# schem.net
KiCad netlist of a schematic drawn in Altium Designer
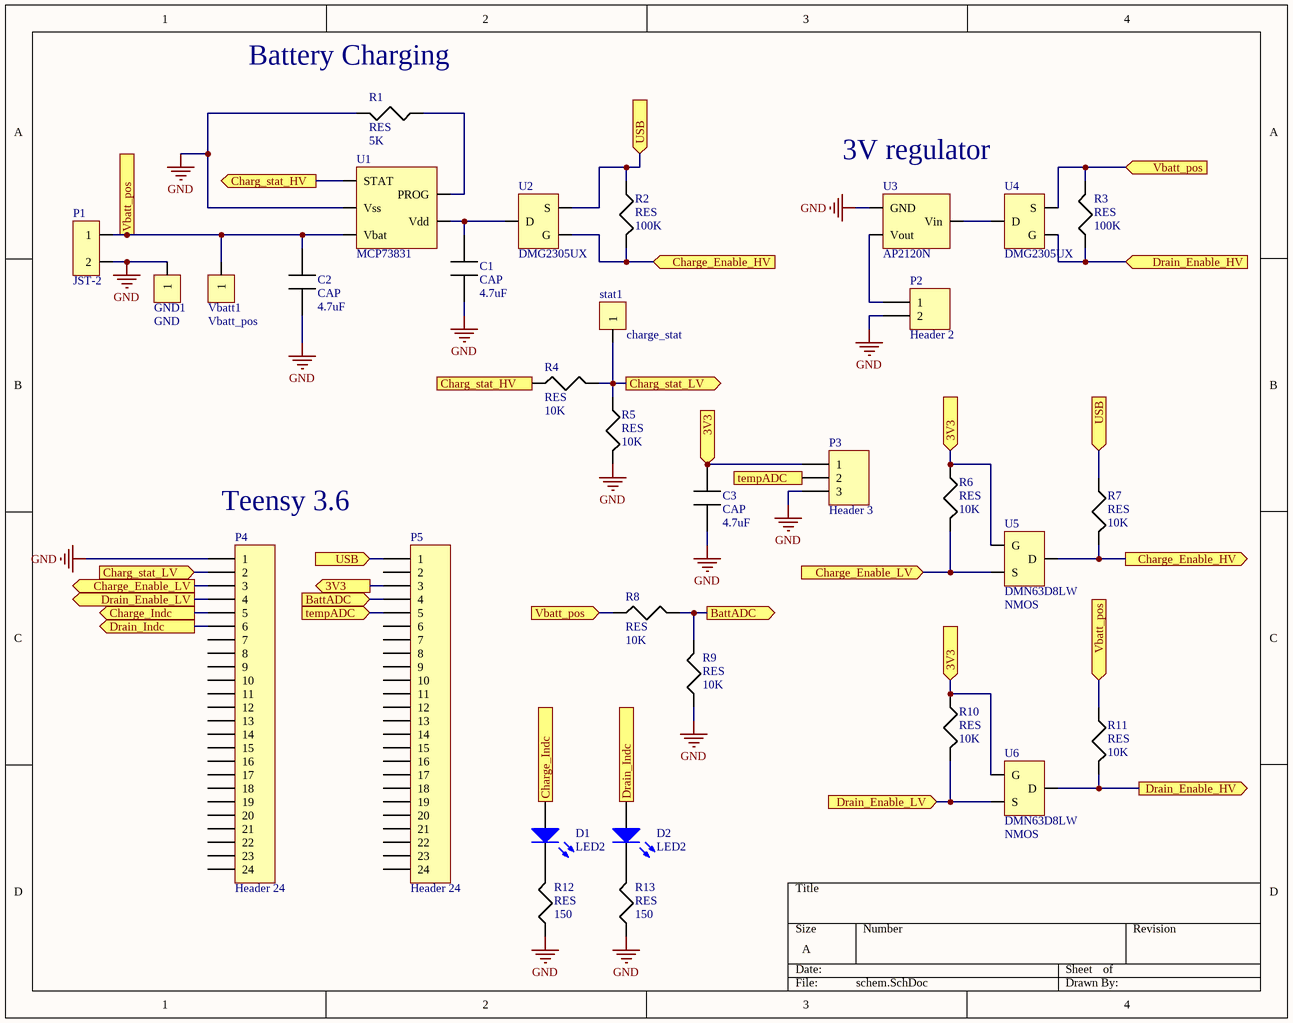
[diagram p0: schem.SchDoc]

(export (version "E")
  (design (tool "Eeschema 10.0.6"))
  (components
    (comp (ref "C1")
      (value "CAP")
      (footprint "Cap 0603 (1608 metric)")
      (fields (field (name "ALTIUM_VALUE") "4.7uF"))
      (libsource (lib "passives") (part "CAP"))
    )
    (comp (ref "C2")
      (value "CAP")
      (footprint "Cap 0603 (1608 metric)")
      (fields (field (name "ALTIUM_VALUE") "4.7uF"))
      (libsource (lib "passives") (part "CAP"))
    )
    (comp (ref "C3")
      (value "CAP")
      (footprint "Cap 0603 (1608 metric)")
      (fields (field (name "ALTIUM_VALUE") "4.7uF"))
      (libsource (lib "passives") (part "CAP"))
    )
    (comp (ref "D1")
      (value "LED2")
      (footprint "3.2X1.6X1.1")
      (description "Typical RED, GREEN, YELLOW, AMBER GaAs LED")
      (fields (field (name "PUBLISHER") "Altium Limited"))
      (libsource (lib "Miscellaneous Devices") (part "LED2"))
    )
    (comp (ref "D2")
      (value "LED2")
      (footprint "3.2X1.6X1.1")
      (description "Typical RED, GREEN, YELLOW, AMBER GaAs LED")
      (fields (field (name "PUBLISHER") "Altium Limited"))
      (libsource (lib "Miscellaneous Devices") (part "LED2"))
    )
    (comp (ref "GND1")
      (value "GND")
      (footprint "test pad")
      (description "test pad")
      (libsource (lib "test_pad") (part "test_pad"))
    )
    (comp (ref "P1") (value "JST-2") (footprint "JST-2 SMT") (libsource (lib "JST") (part "JST-2")))
    (comp (ref "P2")
      (value "Header 2")
      (footprint "HDR1X2")
      (description "Header, 2-Pin")
      (fields (field (name "PUBLISHER") "Altium Limited"))
      (libsource (lib "Miscellaneous Connectors") (part "Header 2"))
    )
    (comp (ref "P3")
      (value "Header 3")
      (footprint "HDR1X3")
      (description "Header, 3-Pin")
      (fields (field (name "PUBLISHER") "Altium Limited"))
      (libsource (lib "Miscellaneous Connectors") (part "Header 3"))
    )
    (comp (ref "P4")
      (value "Header 24")
      (footprint "HDR1X24")
      (description "Header, 24-Pin")
      (fields (field (name "PUBLISHER") "Altium Limited"))
      (libsource (lib "Miscellaneous Connectors") (part "Header 24"))
    )
    (comp (ref "P5")
      (value "Header 24")
      (footprint "HDR1X24")
      (description "Header, 24-Pin")
      (fields (field (name "PUBLISHER") "Altium Limited"))
      (libsource (lib "Miscellaneous Connectors") (part "Header 24"))
    )
    (comp (ref "R1")
      (value "RES")
      (footprint "Res 0603 (1608 metric)")
      (fields (field (name "ALTIUM_VALUE") "5K"))
      (libsource (lib "passives") (part "RES"))
    )
    (comp (ref "R2")
      (value "RES")
      (footprint "Res 0603 (1608 metric)")
      (fields (field (name "ALTIUM_VALUE") "100K"))
      (libsource (lib "passives") (part "RES"))
    )
    (comp (ref "R3")
      (value "RES")
      (footprint "Res 0603 (1608 metric)")
      (fields (field (name "ALTIUM_VALUE") "100K"))
      (libsource (lib "passives") (part "RES"))
    )
    (comp (ref "R4")
      (value "RES")
      (footprint "Res 0603 (1608 metric)")
      (fields (field (name "ALTIUM_VALUE") "10K"))
      (libsource (lib "passives") (part "RES"))
    )
    (comp (ref "R5")
      (value "RES")
      (footprint "Res 0603 (1608 metric)")
      (fields (field (name "ALTIUM_VALUE") "10K"))
      (libsource (lib "passives") (part "RES"))
    )
    (comp (ref "R6")
      (value "RES")
      (footprint "Res 0603 (1608 metric)")
      (fields (field (name "ALTIUM_VALUE") "10K"))
      (libsource (lib "passives") (part "RES"))
    )
    (comp (ref "R7")
      (value "RES")
      (footprint "Res 0603 (1608 metric)")
      (fields (field (name "ALTIUM_VALUE") "10K"))
      (libsource (lib "passives") (part "RES"))
    )
    (comp (ref "R8")
      (value "RES")
      (footprint "Res 0603 (1608 metric)")
      (fields (field (name "ALTIUM_VALUE") "10K"))
      (libsource (lib "passives") (part "RES"))
    )
    (comp (ref "R9")
      (value "RES")
      (footprint "Res 0603 (1608 metric)")
      (fields (field (name "ALTIUM_VALUE") "10K"))
      (libsource (lib "passives") (part "RES"))
    )
    (comp (ref "R10")
      (value "RES")
      (footprint "Res 0603 (1608 metric)")
      (fields (field (name "ALTIUM_VALUE") "10K"))
      (libsource (lib "passives") (part "RES"))
    )
    (comp (ref "R11")
      (value "RES")
      (footprint "Res 0603 (1608 metric)")
      (fields (field (name "ALTIUM_VALUE") "10K"))
      (libsource (lib "passives") (part "RES"))
    )
    (comp (ref "R12")
      (value "RES")
      (footprint "Res 0603 (1608 metric)")
      (fields (field (name "ALTIUM_VALUE") "150"))
      (libsource (lib "passives") (part "RES"))
    )
    (comp (ref "R13")
      (value "RES")
      (footprint "Res 0603 (1608 metric)")
      (fields (field (name "ALTIUM_VALUE") "150"))
      (libsource (lib "passives") (part "RES"))
    )
    (comp (ref "stat1")
      (value "charge_stat")
      (footprint "test pad")
      (description "test pad")
      (libsource (lib "") (part "test_pad_1"))
    )
    (comp (ref "U1")
      (value "MCP73831")
      (footprint "SOT23127P600-8N")
      (description "Li-Charge Management Controllers")
      (libsource (lib "MCP73831") (part "MCP73831"))
    )
    (comp (ref "U2")
      (value "DMG2305UX")
      (footprint "SOT105P240X110-3N")
      (description "P-MOSFET")
      (libsource (lib "Diodes-Inc-FET") (part "DMG2305UX"))
    )
    (comp (ref "U3")
      (value "AP2120N")
      (footprint "AP2120")
      (description "3.0V regulator")
      (libsource (lib "Diodes-Inc-Regulator") (part "AP2120N"))
    )
    (comp (ref "U4")
      (value "DMG2305UX")
      (footprint "SOT105P240X110-3N")
      (description "P-MOSFET")
      (libsource (lib "Diodes-Inc-FET") (part "DMG2305UX"))
    )
    (comp (ref "U5")
      (value "DMN63D8LW")
      (footprint "DMN63D8LW")
      (description "N-MOSFET SOT-323")
      (fields (field (name "ALTIUM_UNNAMED_1") "NMOS"))
      (libsource (lib "Diodes-Inc-FET") (part "DMN63D8LW"))
    )
    (comp (ref "U6")
      (value "DMN63D8LW")
      (footprint "DMN63D8LW")
      (description "N-MOSFET SOT-323")
      (fields (field (name "ALTIUM_UNNAMED_1") "NMOS"))
      (libsource (lib "Diodes-Inc-FET") (part "DMN63D8LW"))
    )
    (comp (ref "Vbatt1")
      (value "Vbatt_pos")
      (footprint "test pad")
      (description "test pad")
      (libsource (lib "test_pad") (part "test_pad"))
    )
  )
  (nets
    (net (code "1") (name "/3V3") (class "Default")
      (node (ref "C3") (pin "2") (pinfunction "2_2") (pintype "passive"))
      (node (ref "P3") (pin "1") (pinfunction "1_1") (pintype "passive"))
      (node (ref "P5") (pin "3") (pinfunction "3_3") (pintype "passive"))
      (node (ref "R10") (pin "1") (pinfunction "1_1") (pintype "passive"))
      (node (ref "R6") (pin "1") (pinfunction "1_1") (pintype "passive"))
      (node (ref "U5") (pin "1") (pinfunction "G_1") (pintype "passive"))
      (node (ref "U6") (pin "1") (pinfunction "G_1") (pintype "passive"))
    )
    (net (code "2") (name "/BattADC") (class "Default")
      (node (ref "P5") (pin "4") (pinfunction "4_4") (pintype "passive"))
      (node (ref "R8") (pin "2") (pinfunction "2_2") (pintype "passive"))
      (node (ref "R9") (pin "2") (pinfunction "2_2") (pintype "passive"))
    )
    (net (code "3") (name "/Charg_stat_HV") (class "Default")
      (node (ref "R4") (pin "1") (pinfunction "1_1") (pintype "passive"))
      (node (ref "U1") (pin "1") (pinfunction "STAT_1") (pintype "passive"))
    )
    (net (code "4") (name "/Charg_stat_LV") (class "Default")
      (node (ref "P4") (pin "2") (pinfunction "2_2") (pintype "passive"))
      (node (ref "R4") (pin "2") (pinfunction "2_2") (pintype "passive"))
      (node (ref "R5") (pin "1") (pinfunction "1_1") (pintype "passive"))
      (node (ref "stat1") (pin "1") (pinfunction "1_1") (pintype "passive"))
    )
    (net (code "5") (name "/Charge_Enable_HV") (class "Default")
      (node (ref "R2") (pin "2") (pinfunction "2_2") (pintype "passive"))
      (node (ref "R7") (pin "2") (pinfunction "2_2") (pintype "passive"))
      (node (ref "U2") (pin "1") (pinfunction "G_1") (pintype "passive"))
      (node (ref "U5") (pin "3") (pinfunction "D_3") (pintype "passive"))
    )
    (net (code "6") (name "/Charge_Enable_LV") (class "Default")
      (node (ref "P4") (pin "3") (pinfunction "3_3") (pintype "passive"))
      (node (ref "R6") (pin "2") (pinfunction "2_2") (pintype "passive"))
      (node (ref "U5") (pin "2") (pinfunction "S_2") (pintype "passive"))
    )
    (net (code "7") (name "/Charge_Indc") (class "Default")
      (node (ref "D1") (pin "1") (pinfunction "A_1") (pintype "passive"))
      (node (ref "P4") (pin "5") (pinfunction "5_5") (pintype "passive"))
    )
    (net (code "8") (name "/Drain_Enable_HV") (class "Default")
      (node (ref "R11") (pin "2") (pinfunction "2_2") (pintype "passive"))
      (node (ref "R3") (pin "1") (pinfunction "1_1") (pintype "passive"))
      (node (ref "U4") (pin "1") (pinfunction "G_1") (pintype "passive"))
      (node (ref "U6") (pin "3") (pinfunction "D_3") (pintype "passive"))
    )
    (net (code "9") (name "/Drain_Enable_LV") (class "Default")
      (node (ref "P4") (pin "4") (pinfunction "4_4") (pintype "passive"))
      (node (ref "R10") (pin "2") (pinfunction "2_2") (pintype "passive"))
      (node (ref "U6") (pin "2") (pinfunction "S_2") (pintype "passive"))
    )
    (net (code "10") (name "/Drain_Indc") (class "Default")
      (node (ref "D2") (pin "1") (pinfunction "A_1") (pintype "passive"))
      (node (ref "P4") (pin "6") (pinfunction "6_6") (pintype "passive"))
    )
    (net (code "11") (name "/USB") (class "Default")
      (node (ref "P5") (pin "1") (pinfunction "1_1") (pintype "passive"))
      (node (ref "R2") (pin "1") (pinfunction "1_1") (pintype "passive"))
      (node (ref "R7") (pin "1") (pinfunction "1_1") (pintype "passive"))
      (node (ref "U2") (pin "2") (pinfunction "S_2") (pintype "passive"))
    )
    (net (code "12") (name "/Vbatt_pos") (class "Default")
      (node (ref "C2") (pin "2") (pinfunction "2_2") (pintype "passive"))
      (node (ref "P1") (pin "1") (pinfunction "1_1") (pintype "passive"))
      (node (ref "R11") (pin "1") (pinfunction "1_1") (pintype "passive"))
      (node (ref "R3") (pin "2") (pinfunction "2_2") (pintype "passive"))
      (node (ref "R8") (pin "1") (pinfunction "1_1") (pintype "passive"))
      (node (ref "U1") (pin "3") (pinfunction "Vbat_3") (pintype "passive"))
      (node (ref "U4") (pin "2") (pinfunction "S_2") (pintype "passive"))
      (node (ref "Vbatt1") (pin "1") (pinfunction "1_1") (pintype "passive"))
    )
    (net (code "13") (name "/tempADC") (class "Default")
      (node (ref "P3") (pin "2") (pinfunction "2_2") (pintype "passive"))
      (node (ref "P5") (pin "5") (pinfunction "5_5") (pintype "passive"))
    )
    (net (code "14") (name "GND") (class "Default")
      (node (ref "C1") (pin "1") (pinfunction "1_1") (pintype "passive"))
      (node (ref "C2") (pin "1") (pinfunction "1_1") (pintype "passive"))
      (node (ref "C3") (pin "1") (pinfunction "1_1") (pintype "passive"))
      (node (ref "GND1") (pin "1") (pinfunction "1_1") (pintype "passive"))
      (node (ref "P1") (pin "2") (pinfunction "2_2") (pintype "passive"))
      (node (ref "P2") (pin "2") (pinfunction "2_2") (pintype "passive"))
      (node (ref "P3") (pin "3") (pinfunction "3_3") (pintype "passive"))
      (node (ref "P4") (pin "1") (pinfunction "1_1") (pintype "passive"))
      (node (ref "R1") (pin "2") (pinfunction "2_2") (pintype "passive"))
      (node (ref "R12") (pin "1") (pinfunction "1_1") (pintype "passive"))
      (node (ref "R13") (pin "1") (pinfunction "1_1") (pintype "passive"))
      (node (ref "R5") (pin "2") (pinfunction "2_2") (pintype "passive"))
      (node (ref "R9") (pin "1") (pinfunction "1_1") (pintype "passive"))
      (node (ref "U1") (pin "2") (pinfunction "Vss_2") (pintype "passive"))
      (node (ref "U3") (pin "1") (pinfunction "GND_1") (pintype "passive"))
    )
    (net (code "15") (name "Net-(D1-K)") (class "Default")
      (node (ref "D1") (pin "2") (pinfunction "K_2") (pintype "passive"))
      (node (ref "R12") (pin "2") (pinfunction "2_2") (pintype "passive"))
    )
    (net (code "16") (name "Net-(D2-K)") (class "Default")
      (node (ref "D2") (pin "2") (pinfunction "K_2") (pintype "passive"))
      (node (ref "R13") (pin "2") (pinfunction "2_2") (pintype "passive"))
    )
    (net (code "17") (name "Net-(U1-PROG)") (class "Default")
      (node (ref "R1") (pin "1") (pinfunction "1_1") (pintype "passive"))
      (node (ref "U1") (pin "5") (pinfunction "PROG_5") (pintype "passive"))
    )
    (net (code "18") (name "Net-(U1-Vdd)") (class "Default")
      (node (ref "C1") (pin "2") (pinfunction "2_2") (pintype "passive"))
      (node (ref "U1") (pin "4") (pinfunction "Vdd_4") (pintype "passive"))
      (node (ref "U2") (pin "3") (pinfunction "D_3") (pintype "passive"))
    )
    (net (code "19") (name "Net-(U3-Vin)") (class "Default")
      (node (ref "U3") (pin "3") (pinfunction "Vin_3") (pintype "passive"))
      (node (ref "U4") (pin "3") (pinfunction "D_3") (pintype "passive"))
    )
    (net (code "20") (name "Net-(U3-Vout)") (class "Default")
      (node (ref "P2") (pin "1") (pinfunction "1_1") (pintype "passive"))
      (node (ref "U3") (pin "2") (pinfunction "Vout_2") (pintype "passive"))
    )
    (net (code "21") (name "unconnected-(P4-Pad7)") (class "Default")
      (node (ref "P4") (pin "7") (pinfunction "7_7") (pintype "passive"))
    )
    (net (code "22") (name "unconnected-(P4-Pad8)") (class "Default")
      (node (ref "P4") (pin "8") (pinfunction "8_8") (pintype "passive"))
    )
    (net (code "23") (name "unconnected-(P4-Pad9)") (class "Default")
      (node (ref "P4") (pin "9") (pinfunction "9_9") (pintype "passive"))
    )
    (net (code "24") (name "unconnected-(P4-Pad10)") (class "Default")
      (node (ref "P4") (pin "10") (pinfunction "10_10") (pintype "passive"))
    )
    (net (code "25") (name "unconnected-(P4-Pad11)") (class "Default")
      (node (ref "P4") (pin "11") (pinfunction "11_11") (pintype "passive"))
    )
    (net (code "26") (name "unconnected-(P4-Pad12)") (class "Default")
      (node (ref "P4") (pin "12") (pinfunction "12_12") (pintype "passive"))
    )
    (net (code "27") (name "unconnected-(P4-Pad13)") (class "Default")
      (node (ref "P4") (pin "13") (pinfunction "13_13") (pintype "passive"))
    )
    (net (code "28") (name "unconnected-(P4-Pad14)") (class "Default")
      (node (ref "P4") (pin "14") (pinfunction "14_14") (pintype "passive"))
    )
    (net (code "29") (name "unconnected-(P4-Pad15)") (class "Default")
      (node (ref "P4") (pin "15") (pinfunction "15_15") (pintype "passive"))
    )
    (net (code "30") (name "unconnected-(P4-Pad16)") (class "Default")
      (node (ref "P4") (pin "16") (pinfunction "16_16") (pintype "passive"))
    )
    (net (code "31") (name "unconnected-(P4-Pad17)") (class "Default")
      (node (ref "P4") (pin "17") (pinfunction "17_17") (pintype "passive"))
    )
    (net (code "32") (name "unconnected-(P4-Pad18)") (class "Default")
      (node (ref "P4") (pin "18") (pinfunction "18_18") (pintype "passive"))
    )
    (net (code "33") (name "unconnected-(P4-Pad19)") (class "Default")
      (node (ref "P4") (pin "19") (pinfunction "19_19") (pintype "passive"))
    )
    (net (code "34") (name "unconnected-(P4-Pad20)") (class "Default")
      (node (ref "P4") (pin "20") (pinfunction "20_20") (pintype "passive"))
    )
    (net (code "35") (name "unconnected-(P4-Pad21)") (class "Default")
      (node (ref "P4") (pin "21") (pinfunction "21_21") (pintype "passive"))
    )
    (net (code "36") (name "unconnected-(P4-Pad22)") (class "Default")
      (node (ref "P4") (pin "22") (pinfunction "22_22") (pintype "passive"))
    )
    (net (code "37") (name "unconnected-(P4-Pad23)") (class "Default")
      (node (ref "P4") (pin "23") (pinfunction "23_23") (pintype "passive"))
    )
    (net (code "38") (name "unconnected-(P4-Pad24)") (class "Default")
      (node (ref "P4") (pin "24") (pinfunction "24_24") (pintype "passive"))
    )
    (net (code "39") (name "unconnected-(P5-Pad2)") (class "Default")
      (node (ref "P5") (pin "2") (pinfunction "2_2") (pintype "passive"))
    )
    (net (code "40") (name "unconnected-(P5-Pad6)") (class "Default")
      (node (ref "P5") (pin "6") (pinfunction "6_6") (pintype "passive"))
    )
    (net (code "41") (name "unconnected-(P5-Pad7)") (class "Default")
      (node (ref "P5") (pin "7") (pinfunction "7_7") (pintype "passive"))
    )
    (net (code "42") (name "unconnected-(P5-Pad8)") (class "Default")
      (node (ref "P5") (pin "8") (pinfunction "8_8") (pintype "passive"))
    )
    (net (code "43") (name "unconnected-(P5-Pad9)") (class "Default")
      (node (ref "P5") (pin "9") (pinfunction "9_9") (pintype "passive"))
    )
    (net (code "44") (name "unconnected-(P5-Pad10)") (class "Default")
      (node (ref "P5") (pin "10") (pinfunction "10_10") (pintype "passive"))
    )
    (net (code "45") (name "unconnected-(P5-Pad11)") (class "Default")
      (node (ref "P5") (pin "11") (pinfunction "11_11") (pintype "passive"))
    )
    (net (code "46") (name "unconnected-(P5-Pad12)") (class "Default")
      (node (ref "P5") (pin "12") (pinfunction "12_12") (pintype "passive"))
    )
    (net (code "47") (name "unconnected-(P5-Pad13)") (class "Default")
      (node (ref "P5") (pin "13") (pinfunction "13_13") (pintype "passive"))
    )
    (net (code "48") (name "unconnected-(P5-Pad14)") (class "Default")
      (node (ref "P5") (pin "14") (pinfunction "14_14") (pintype "passive"))
    )
    (net (code "49") (name "unconnected-(P5-Pad15)") (class "Default")
      (node (ref "P5") (pin "15") (pinfunction "15_15") (pintype "passive"))
    )
    (net (code "50") (name "unconnected-(P5-Pad16)") (class "Default")
      (node (ref "P5") (pin "16") (pinfunction "16_16") (pintype "passive"))
    )
    (net (code "51") (name "unconnected-(P5-Pad17)") (class "Default")
      (node (ref "P5") (pin "17") (pinfunction "17_17") (pintype "passive"))
    )
    (net (code "52") (name "unconnected-(P5-Pad18)") (class "Default")
      (node (ref "P5") (pin "18") (pinfunction "18_18") (pintype "passive"))
    )
    (net (code "53") (name "unconnected-(P5-Pad19)") (class "Default")
      (node (ref "P5") (pin "19") (pinfunction "19_19") (pintype "passive"))
    )
    (net (code "54") (name "unconnected-(P5-Pad20)") (class "Default")
      (node (ref "P5") (pin "20") (pinfunction "20_20") (pintype "passive"))
    )
    (net (code "55") (name "unconnected-(P5-Pad21)") (class "Default")
      (node (ref "P5") (pin "21") (pinfunction "21_21") (pintype "passive"))
    )
    (net (code "56") (name "unconnected-(P5-Pad22)") (class "Default")
      (node (ref "P5") (pin "22") (pinfunction "22_22") (pintype "passive"))
    )
    (net (code "57") (name "unconnected-(P5-Pad23)") (class "Default")
      (node (ref "P5") (pin "23") (pinfunction "23_23") (pintype "passive"))
    )
    (net (code "58") (name "unconnected-(P5-Pad24)") (class "Default")
      (node (ref "P5") (pin "24") (pinfunction "24_24") (pintype "passive"))
    )
  )
)
